# AFE_Channel_5.net
KiCad netlist of a schematic drawn in Altium Designer
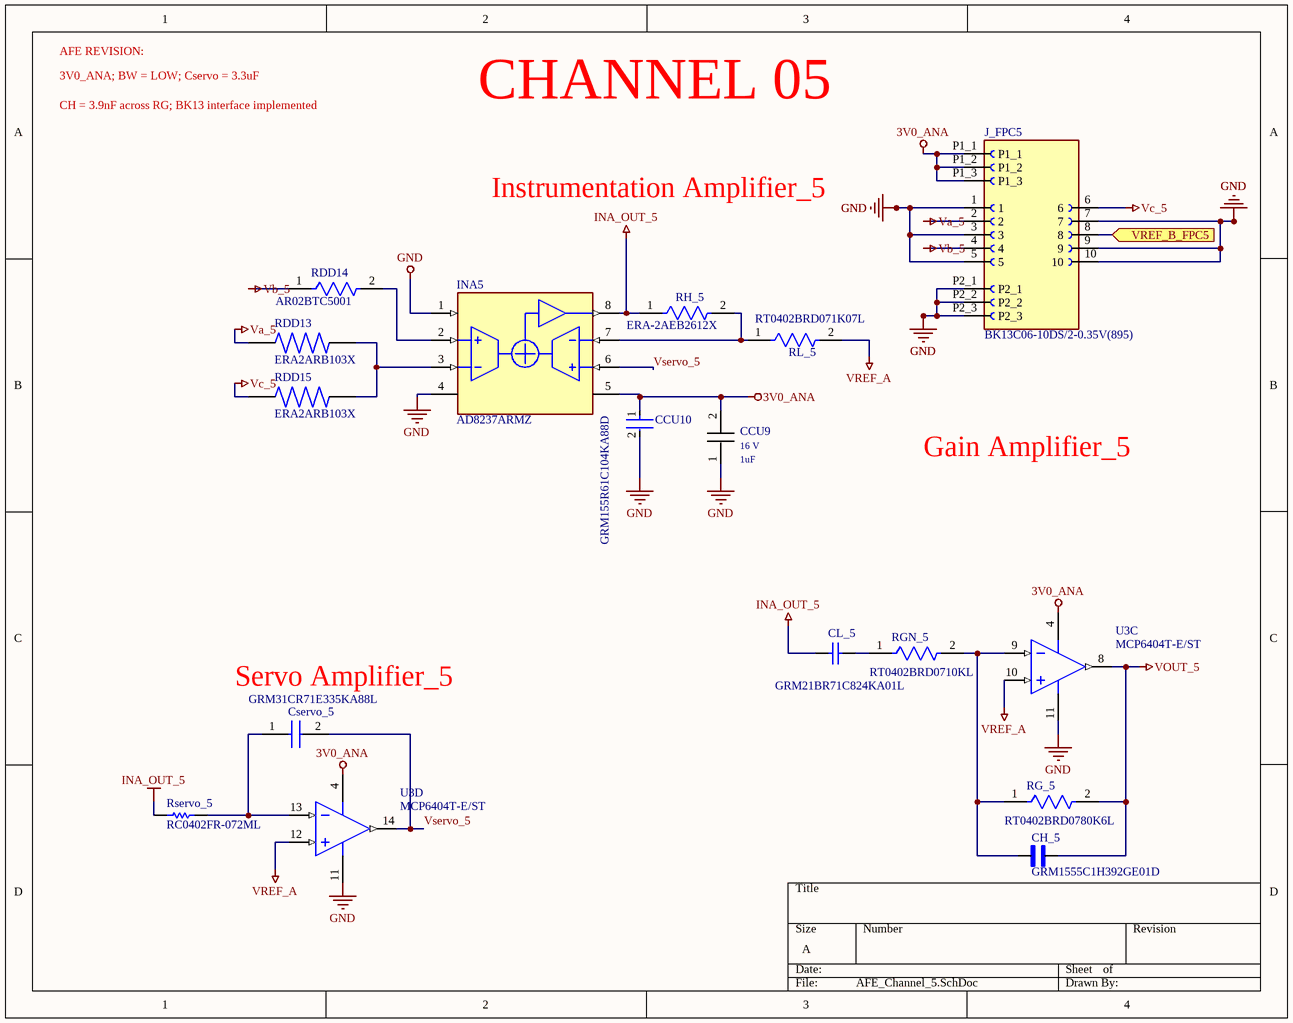
[diagram p0: AFE_Channel_5.SchDoc]

(export (version "E")
  (design (tool "Eeschema 10.0.6"))
  (components
    (comp (ref "CCU9")
      (value "MURATA_GRM155C71C105KE11D")
      (footprint "MURATA_GRM155C71C105KE11D_0:*MURATA_GRM155C71C105KE11D_0")
      (description "Murata GRM155C71C105KE11D: 1 uF 16 V X7S +/-10%, 0402/1005 metric")
      (fields (field (name "MF") "Murata") (field (name "MP") "GRM155C71C105KE11D"))
      (libsource (lib "EMG_Controlled_R5") (part "EMG_R5_CCU9"))
    )
    (comp (ref "CCU10")
      (value "GRM155R61C104KA88D")
      (footprint "96DF66F8-B997-472F-A885-42BCAAE661B2_FP-GRM155-0_05-IPC_C:FP-GRM155-0_05-IPC_C")
      (description "CAP CER 0.1UF 16V X5R 0402")
      (fields (field (name "VOLTAGE") "16V") (field (name "TOLERANCE") "10%"))
      (libsource (lib "EMG_Controlled_R5") (part "EMG_R5_CCU10"))
    )
    (comp (ref "CH_5")
      (value "GRM1555C1H392GE01D")
      (footprint "GRM1555C1H392GE01D_0:CAPC1005X55N")
      (description "SMD capacitor C0G(EIA) with capacitance 3900pF Tol.2%. Rated voltage 50Vdc 125C")
      (fields (field (name "MF") "Murata Electronics"))
      (libsource (lib "EMG_Controlled_R5") (part "EMG_R5_CH_5"))
    )
    (comp (ref "CL_5")
      (value "GRM21BR71C824KA01L")
      (footprint "987105EF-01FA-4198-A59F-44D3B68BB40E_CAPC2013X135X45ML10T25:CAPC2013X135X45ML10T25")
      (fields (field (name "MANUFACTURER") "Murata"))
      (libsource (lib "EMG_Controlled_R5") (part "EMG_R5_CL_5"))
    )
    (comp (ref "Cservo_5")
      (value "GRM31CR71E335KA88L")
      (footprint "SamacSys:GRM31x")
      (description "Capacitor")
      (fields
        (field (name "MOUSER PART NUMBER") "81-GRM31CR71E335KA8L")
        (field (name "MANUFACTURER") "Murata")
      )
      (libsource (lib "EMG_Controlled_R5") (part "EMG_R5_Cservo_5"))
    )
    (comp (ref "INA5")
      (value "AD8237ARMZ")
      (footprint "EMG_AD8237_R3:EMG_AD8237_R3_MSOP8")
      (description "Micropower, Zero Drift, True Rail-to-Rail Instrumentation Amplifier")
      (fields (field (name "MF") "Analog Devices"))
      (libsource (lib "EMG_Controlled_R5") (part "EMG_R5_INA5"))
    )
    (comp (ref "J_FPC5")
      (value "BK13C06-10DS/2-0.35V(895)")
      (footprint "BK13C06-10DS_2-0.35V_895__0:HIROSE_BK13C06-10DS/2-0.35V(895)")
      (description "10 Position Connector Receptacle, Center Strip Contacts Surface Mount Gold")
      (fields (field (name "MF") "Hirose Electric Co Ltd"))
      (libsource (lib "EMG_Controlled_R5") (part "EMG_R5_J_FPC5"))
    )
    (comp (ref "RDD13")
      (value "ERA2ARB103X")
      (footprint "ERA2ARB103X_0:RES_ERA2ARB103X")
      (libsource (lib "EMG_Controlled_R5") (part "EMG_R5_RDD13"))
    )
    (comp (ref "RDD14")
      (value "AR02BTC5001")
      (footprint "7D606042-220B-45EE-95DD-CA1A974E4C0D_FP-AC0402-MFG:FP-AC0402-MFG")
      (description "-55℃~+155℃ 50V 5kΩ 63mW Thin Film Resistor ±0.1% ±25ppm/℃ 0402 Chip Resistor - Surface Mount ROH")
      (fields
        (field (name "MANUFACTURER") "Viking Tech")
        (field (name "OCTOPART") "https://octopart.com/datasheet/viking-tech/AR02BTC5001")
      )
      (libsource (lib "EMG_Controlled_R5") (part "EMG_R5_RDD14"))
    )
    (comp (ref "RDD15")
      (value "ERA2ARB103X")
      (footprint "ERA2ARB103X_0:RES_ERA2ARB103X")
      (libsource (lib "EMG_Controlled_R5") (part "EMG_R5_RDD15"))
    )
    (comp (ref "RGN_5")
      (value "RT0402BRD0710KL")
      (footprint "B876F212-A29A-4983-9BB8-539D1BA2EBA1_FP-RT0402-MFG:FP-RT0402-MFG")
      (description "RES 10.0K OHM 1/16W .1% SMD 0402")
      (fields
        (field (name "MANUFACTURER") "Yageo")
        (field (name "OCTOPART") "https://octopart.com/rt0402brd0710kl-yageo-1181432")
      )
      (libsource (lib "EMG_Controlled_R5") (part "EMG_R5_RGN_5"))
    )
    (comp (ref "RG_5")
      (value "RT0402BRD0780K6L")
      (footprint "B876F212-A29A-4983-9BB8-539D1BA2EBA1_FP-RT0402-MFG:FP-RT0402-MFG")
      (description "RES SMD 80.6KOHM 0.1% 1/16W 0402")
      (fields
        (field (name "MANUFACTURER") "Yageo")
        (field (name "OCTOPART") "https://octopart.com/rt0402brd0780k6l-yageo-1468076")
      )
      (libsource (lib "EMG_Controlled_R5") (part "EMG_R5_RG_5"))
    )
    (comp (ref "RH_5")
      (value "ERA-2AEB2612X")
      (footprint "1CBBEC27-AD79-48E8-A701-2E235EA9F8F2_FP-AC0402-IPC_A:FP-AC0402-IPC_A")
      (description "RES 26.1kΩ ±0.1% 0.063W 0402")
      (fields (field (name "TOLERANCE") "0.1%") (field (name "MANUFACTURER") "PANASONIC"))
      (libsource (lib "EMG_Controlled_R5") (part "EMG_R5_RH_5"))
    )
    (comp (ref "RL_5")
      (value "RT0402BRD071K07L")
      (footprint "B876F212-A29A-4983-9BB8-539D1BA2EBA1_FP-RT0402-MFG:FP-RT0402-MFG")
      (description "RES SMD 1.07K OHM 0.1% 1/16W")
      (fields
        (field (name "OCTOPART") "https://octopart.com/rt0402brd071k07l-yageo-1400807")
        (field (name "MANUFACTURER") "Yageo")
      )
      (libsource (lib "EMG_Controlled_R5") (part "EMG_R5_RL_5"))
    )
    (comp (ref "Rservo_5")
      (value "RC0402FR-072ML")
      (footprint "3EB15388-1759-44FF-BAE1-1F0823F3E8F1_RESC1005X40X25NL05T10:RESC1005X40X25NL05T10")
      (fields (field (name "MANUFACTURER") "Yageo / Phycomp"))
      (libsource (lib "EMG_Controlled_R5") (part "EMG_R5_Rservo_5"))
    )
    (comp (ref "U3")
      (value "MCP6404T-E/ST")
      (footprint "CEF93338-31F0-4C64-85B6-F650E0BB75E3_TSSOP-ST14_N:TSSOP-ST14_N")
      (description "None")
      (libsource (lib "EMG_Controlled_R5") (part "EMG_R5_U3"))
    )
  )
  (nets
    (net (code "1") (name "/VREF_B_FPC5") (class "Default")
      (node (ref "J_FPC5") (pin "8") (pinfunction "8_8") (pintype "passive"))
    )
    (net (code "2") (name "/Vservo_5") (class "Default")
      (node (ref "Cservo_5") (pin "2") (pinfunction "2_2") (pintype "passive"))
      (node (ref "INA5") (pin "6") (pinfunction "REF_6") (pintype "input"))
      (node (ref "U3") (pin "14") (pinfunction "VOUTD_14") (pintype "output"))
    )
    (net (code "3") (name "3V0_ANA") (class "Default")
      (node (ref "CCU10") (pin "1") (pinfunction "1_1") (pintype "passive"))
      (node (ref "CCU9") (pin "2") (pinfunction "2_2") (pintype "passive"))
      (node (ref "INA5") (pin "5") (pinfunction "+VS_5") (pintype "power_in"))
      (node (ref "J_FPC5") (pin "P1_1") (pinfunction "P1_1_P1_1") (pintype "power_in"))
      (node (ref "J_FPC5") (pin "P1_2") (pinfunction "P1_2_P1_2") (pintype "power_in"))
      (node (ref "J_FPC5") (pin "P1_3") (pinfunction "P1_3_P1_3") (pintype "power_in"))
      (node (ref "U3") (pin "4") (pinfunction "VDD_4") (pintype "power_in"))
    )
    (net (code "4") (name "GND") (class "Default")
      (node (ref "CCU10") (pin "2") (pinfunction "2_2") (pintype "passive"))
      (node (ref "CCU9") (pin "1") (pinfunction "1_1") (pintype "passive"))
      (node (ref "INA5") (pin "1") (pinfunction "BW_1") (pintype "input"))
      (node (ref "INA5") (pin "4") (pinfunction "-VS_4") (pintype "power_in"))
      (node (ref "J_FPC5") (pin "1") (pinfunction "1_1") (pintype "passive"))
      (node (ref "J_FPC5") (pin "10") (pinfunction "10_10") (pintype "passive"))
      (node (ref "J_FPC5") (pin "3") (pinfunction "3_3") (pintype "passive"))
      (node (ref "J_FPC5") (pin "5") (pinfunction "5_5") (pintype "passive"))
      (node (ref "J_FPC5") (pin "7") (pinfunction "7_7") (pintype "passive"))
      (node (ref "J_FPC5") (pin "9") (pinfunction "9_9") (pintype "passive"))
      (node (ref "J_FPC5") (pin "P2_1") (pinfunction "P2_1_P2_1") (pintype "power_in"))
      (node (ref "J_FPC5") (pin "P2_2") (pinfunction "P2_2_P2_2") (pintype "power_in"))
      (node (ref "J_FPC5") (pin "P2_3") (pinfunction "P2_3_P2_3") (pintype "power_in"))
      (node (ref "U3") (pin "11") (pinfunction "VSS_11") (pintype "power_in"))
    )
    (net (code "5") (name "INA_OUT_5") (class "Default")
      (node (ref "CL_5") (pin "2") (pinfunction "2_2") (pintype "passive"))
      (node (ref "INA5") (pin "8") (pinfunction "VOUT_8") (pintype "output"))
      (node (ref "RH_5") (pin "1") (pinfunction "1_1") (pintype "passive"))
      (node (ref "Rservo_5") (pin "2") (pinfunction "2_2") (pintype "passive"))
    )
    (net (code "6") (name "Net-(CL_5-Pad1)") (class "Default")
      (node (ref "CL_5") (pin "1") (pinfunction "1_1") (pintype "passive"))
      (node (ref "RGN_5") (pin "1") (pinfunction "1_1") (pintype "passive"))
    )
    (net (code "7") (name "Net-(INA5-+IN)") (class "Default")
      (node (ref "INA5") (pin "2") (pinfunction "+IN_2") (pintype "input"))
      (node (ref "RDD14") (pin "2") (pinfunction "2_2") (pintype "passive"))
    )
    (net (code "8") (name "Net-(INA5--IN)") (class "Default")
      (node (ref "INA5") (pin "3") (pinfunction "-IN_3") (pintype "input"))
      (node (ref "RDD13") (pin "2") (pinfunction "2_2") (pintype "passive"))
      (node (ref "RDD15") (pin "2") (pinfunction "2_2") (pintype "passive"))
    )
    (net (code "9") (name "Net-(INA5-FB)") (class "Default")
      (node (ref "INA5") (pin "7") (pinfunction "FB_7") (pintype "input"))
      (node (ref "RH_5") (pin "2") (pinfunction "2_2") (pintype "passive"))
      (node (ref "RL_5") (pin "1") (pinfunction "1_1") (pintype "passive"))
    )
    (net (code "10") (name "Net-(U3C-VINC-)") (class "Default")
      (node (ref "CH_5") (pin "2") (pinfunction "2_2") (pintype "passive"))
      (node (ref "RGN_5") (pin "2") (pinfunction "2_2") (pintype "passive"))
      (node (ref "RG_5") (pin "1") (pinfunction "1_1") (pintype "passive"))
      (node (ref "U3") (pin "9") (pinfunction "VINC-_9") (pintype "input"))
    )
    (net (code "11") (name "Net-(U3D-VIND-)") (class "Default")
      (node (ref "Cservo_5") (pin "1") (pinfunction "1_1") (pintype "passive"))
      (node (ref "Rservo_5") (pin "1") (pinfunction "1_1") (pintype "passive"))
      (node (ref "U3") (pin "13") (pinfunction "VIND-_13") (pintype "input"))
    )
    (net (code "12") (name "VOUT_5") (class "Default")
      (node (ref "CH_5") (pin "1") (pinfunction "1_1") (pintype "passive"))
      (node (ref "RG_5") (pin "2") (pinfunction "2_2") (pintype "passive"))
      (node (ref "U3") (pin "8") (pinfunction "VOUTC_8") (pintype "output"))
    )
    (net (code "13") (name "VREF_A") (class "Default")
      (node (ref "RL_5") (pin "2") (pinfunction "2_2") (pintype "passive"))
      (node (ref "U3") (pin "10") (pinfunction "VINC+_10") (pintype "input"))
      (node (ref "U3") (pin "12") (pinfunction "VIND+_12") (pintype "input"))
    )
    (net (code "14") (name "Va_5") (class "Default")
      (node (ref "J_FPC5") (pin "2") (pinfunction "2_2") (pintype "passive"))
      (node (ref "RDD13") (pin "1") (pinfunction "1_1") (pintype "passive"))
    )
    (net (code "15") (name "Vb_5") (class "Default")
      (node (ref "J_FPC5") (pin "4") (pinfunction "4_4") (pintype "passive"))
      (node (ref "RDD14") (pin "1") (pinfunction "1_1") (pintype "passive"))
    )
    (net (code "16") (name "Vc_5") (class "Default")
      (node (ref "J_FPC5") (pin "6") (pinfunction "6_6") (pintype "passive"))
      (node (ref "RDD15") (pin "1") (pinfunction "1_1") (pintype "passive"))
    )
  )
)
